# v6.net
KiCad netlist of a schematic drawn in EAGLE
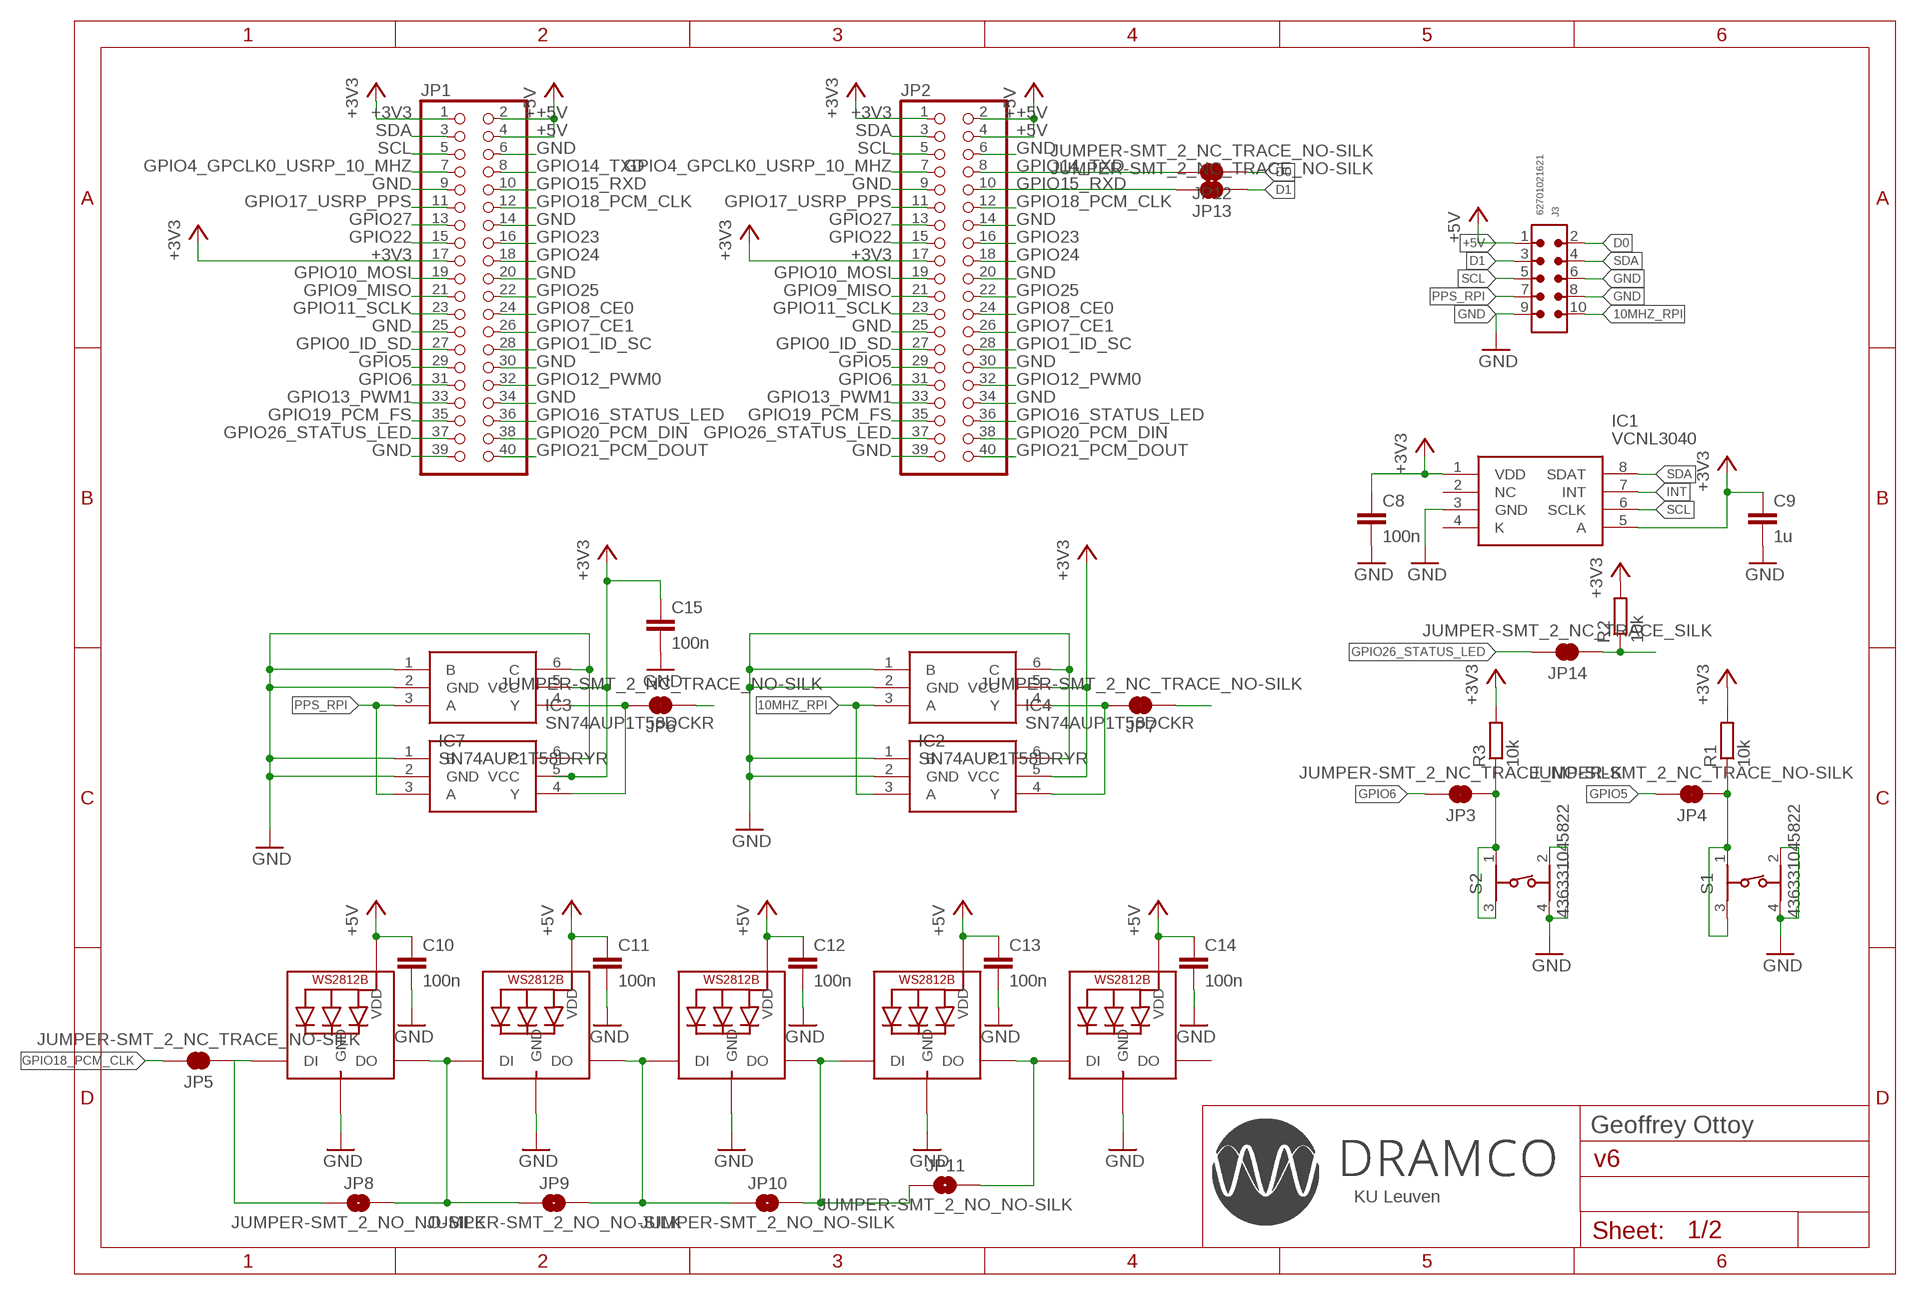
[diagram p0: schematic, sheet 1]
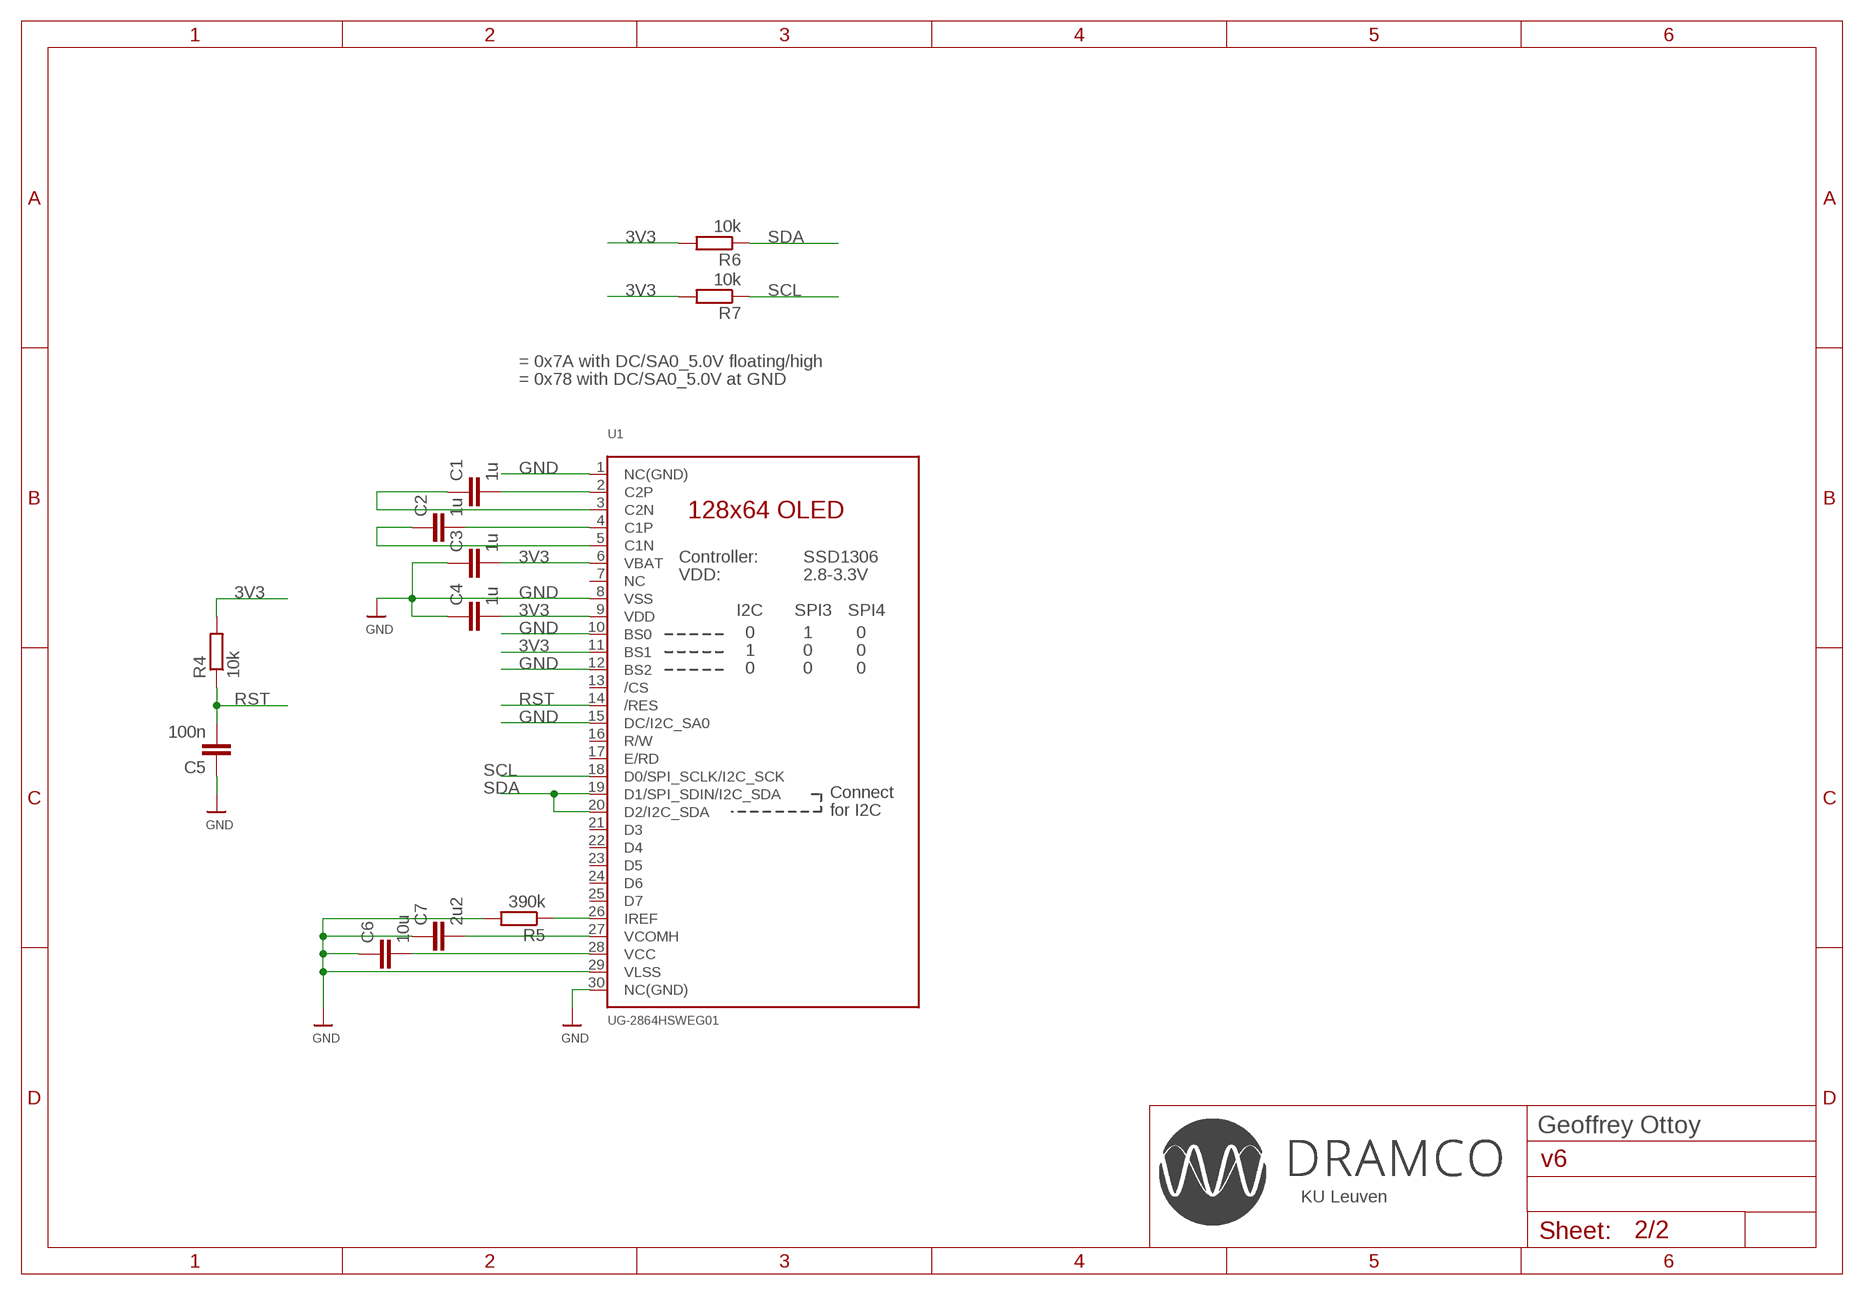
[diagram p1: schematic, sheet 2]

(export (version "E")
  (design (tool "Eeschema 10.0.6"))
  (components
    (comp (ref "C1")
      (value "1u")
      (footprint "eagle-import:C0603")
      (libsource (lib "eagle-import") (part "C-EUC0603"))
    )
    (comp (ref "C2")
      (value "1u")
      (footprint "eagle-import:C0603")
      (libsource (lib "eagle-import") (part "C-EUC0603"))
    )
    (comp (ref "C3")
      (value "1u")
      (footprint "eagle-import:C0603")
      (libsource (lib "eagle-import") (part "C-EUC0603"))
    )
    (comp (ref "C4")
      (value "1u")
      (footprint "eagle-import:C0603")
      (libsource (lib "eagle-import") (part "C-EUC0603"))
    )
    (comp (ref "C5")
      (value "100n")
      (footprint "eagle-import:C0603")
      (libsource (lib "eagle-import") (part "C-EUC0603"))
    )
    (comp (ref "C6")
      (value "10u")
      (footprint "eagle-import:C0603")
      (libsource (lib "eagle-import") (part "C-EUC0603"))
    )
    (comp (ref "C7")
      (value "2u2")
      (footprint "eagle-import:C0603")
      (libsource (lib "eagle-import") (part "C-EUC0603"))
    )
    (comp (ref "R4")
      (value "10k")
      (footprint "eagle-import:R0603")
      (libsource (lib "eagle-import") (part "R-EU_R0603"))
    )
    (comp (ref "R5")
      (value "390k")
      (footprint "eagle-import:R0603")
      (libsource (lib "eagle-import") (part "R-EU_R0603"))
    )
    (comp (ref "R6")
      (value "10k")
      (footprint "eagle-import:R0603")
      (libsource (lib "eagle-import") (part "R-EU_R0603"))
    )
    (comp (ref "R7")
      (value "10k")
      (footprint "eagle-import:R0603")
      (libsource (lib "eagle-import") (part "R-EU_R0603"))
    )
    (comp (ref "U1")
      (value "UG-2864HSWEG01")
      (footprint "eagle-import:UG-2864HSWEG01_0.96IN_WRAPAROUND")
      (libsource (lib "eagle-import") (part "DISP_OLED_UG-2864HSWEG010.96{dblquote}"))
    )
    (comp (ref "C8")
      (value "100n")
      (footprint "eagle-import:C0603")
      (libsource (lib "eagle-import") (part "C-EUC0603"))
    )
    (comp (ref "C9")
      (value "1u")
      (footprint "eagle-import:C0603")
      (libsource (lib "eagle-import") (part "C-EUC0603"))
    )
    (comp (ref "C10")
      (value "100n")
      (footprint "eagle-import:C0603")
      (libsource (lib "eagle-import") (part "C-EUC0603"))
    )
    (comp (ref "C11")
      (value "100n")
      (footprint "eagle-import:C0603")
      (libsource (lib "eagle-import") (part "C-EUC0603"))
    )
    (comp (ref "C12")
      (value "100n")
      (footprint "eagle-import:C0603")
      (libsource (lib "eagle-import") (part "C-EUC0603"))
    )
    (comp (ref "C13")
      (value "100n")
      (footprint "eagle-import:C0603")
      (libsource (lib "eagle-import") (part "C-EUC0603"))
    )
    (comp (ref "C14")
      (value "100n")
      (footprint "eagle-import:C0603")
      (libsource (lib "eagle-import") (part "C-EUC0603"))
    )
    (comp (ref "C15")
      (value "100n")
      (footprint "eagle-import:C0603")
      (libsource (lib "eagle-import") (part "C-EUC0603"))
    )
    (comp (ref "IC1")
      (value "VCNL3040")
      (footprint "eagle-import:SON108P200X400X115-8N")
      (fields (field (name "MOUSER_PART_NUMBER") "78-VCNL3040"))
      (libsource (lib "eagle-import") (part "VCNL3040"))
    )
    (comp (ref "IC2")
      (value "SN74AUP1T58DRYR")
      (footprint "eagle-import:SON50P100X145X60-6N")
      (libsource (lib "eagle-import") (part "SN74AUP1T58DRYR"))
    )
    (comp (ref "IC3")
      (value "SN74AUP1T58DCKR")
      (footprint "eagle-import:SOT65P210X110-6N")
      (libsource (lib "eagle-import") (part "SN74AUP1T58DCKR"))
    )
    (comp (ref "IC4")
      (value "SN74AUP1T58DCKR")
      (footprint "eagle-import:SOT65P210X110-6N")
      (libsource (lib "eagle-import") (part "SN74AUP1T58DCKR"))
    )
    (comp (ref "IC7")
      (value "SN74AUP1T58DRYR")
      (footprint "eagle-import:SON50P100X145X60-6N")
      (libsource (lib "eagle-import") (part "SN74AUP1T58DRYR"))
    )
    (comp (ref "J3")
      (value "62701021621")
      (footprint "eagle-import:62701021621")
      (libsource (lib "eagle-import") (part "6270XX21621_62701021621"))
    )
    (comp (ref "JP1")
      (value "PINHD-2X20")
      (footprint "eagle-import:2X20")
      (libsource (lib "eagle-import") (part "PINHD-2X20"))
    )
    (comp (ref "JP2")
      (value "PINHD-2X20/90")
      (footprint "eagle-import:2X20_90")
      (libsource (lib "eagle-import") (part "PINHD-2X20/90"))
    )
    (comp (ref "JP3")
      (value "JUMPER-SMT_2_NC_TRACE_NO-SILK")
      (footprint "eagle-import:SMT-JUMPER_2_NC_TRACE_NO-SILK")
      (libsource (lib "eagle-import") (part "JUMPER-SMT_2_NC_TRACE_NO-SILK"))
    )
    (comp (ref "JP4")
      (value "JUMPER-SMT_2_NC_TRACE_NO-SILK")
      (footprint "eagle-import:SMT-JUMPER_2_NC_TRACE_NO-SILK")
      (libsource (lib "eagle-import") (part "JUMPER-SMT_2_NC_TRACE_NO-SILK"))
    )
    (comp (ref "JP5")
      (value "JUMPER-SMT_2_NC_TRACE_NO-SILK")
      (footprint "eagle-import:SMT-JUMPER_2_NC_TRACE_NO-SILK")
      (libsource (lib "eagle-import") (part "JUMPER-SMT_2_NC_TRACE_NO-SILK"))
    )
    (comp (ref "JP6")
      (value "JUMPER-SMT_2_NC_TRACE_NO-SILK")
      (footprint "eagle-import:SMT-JUMPER_2_NC_TRACE_NO-SILK")
      (libsource (lib "eagle-import") (part "JUMPER-SMT_2_NC_TRACE_NO-SILK"))
    )
    (comp (ref "JP7")
      (value "JUMPER-SMT_2_NC_TRACE_NO-SILK")
      (footprint "eagle-import:SMT-JUMPER_2_NC_TRACE_NO-SILK")
      (libsource (lib "eagle-import") (part "JUMPER-SMT_2_NC_TRACE_NO-SILK"))
    )
    (comp (ref "JP8")
      (value "JUMPER-SMT_2_NO_NO-SILK")
      (footprint "eagle-import:SMT-JUMPER_2_NO_NO-SILK")
      (libsource (lib "eagle-import") (part "JUMPER-SMT_2_NO_NO-SILK"))
    )
    (comp (ref "JP9")
      (value "JUMPER-SMT_2_NO_NO-SILK")
      (footprint "eagle-import:SMT-JUMPER_2_NO_NO-SILK")
      (libsource (lib "eagle-import") (part "JUMPER-SMT_2_NO_NO-SILK"))
    )
    (comp (ref "JP10")
      (value "JUMPER-SMT_2_NO_NO-SILK")
      (footprint "eagle-import:SMT-JUMPER_2_NO_NO-SILK")
      (libsource (lib "eagle-import") (part "JUMPER-SMT_2_NO_NO-SILK"))
    )
    (comp (ref "JP11")
      (value "JUMPER-SMT_2_NO_NO-SILK")
      (footprint "eagle-import:SMT-JUMPER_2_NO_NO-SILK")
      (libsource (lib "eagle-import") (part "JUMPER-SMT_2_NO_NO-SILK"))
    )
    (comp (ref "JP12")
      (value "JUMPER-SMT_2_NC_TRACE_NO-SILK")
      (footprint "eagle-import:SMT-JUMPER_2_NC_TRACE_NO-SILK")
      (libsource (lib "eagle-import") (part "JUMPER-SMT_2_NC_TRACE_NO-SILK"))
    )
    (comp (ref "JP13")
      (value "JUMPER-SMT_2_NC_TRACE_NO-SILK")
      (footprint "eagle-import:SMT-JUMPER_2_NC_TRACE_NO-SILK")
      (libsource (lib "eagle-import") (part "JUMPER-SMT_2_NC_TRACE_NO-SILK"))
    )
    (comp (ref "JP14")
      (value "JUMPER-SMT_2_NC_TRACE_SILK")
      (footprint "eagle-import:SMT-JUMPER_2_NC_TRACE_SILK")
      (libsource (lib "eagle-import") (part "JUMPER-SMT_2_NC_TRACE_SILK"))
    )
    (comp (ref "LED1")
      (value "WS2812B5050")
      (footprint "eagle-import:WS2812B")
      (libsource (lib "eagle-import") (part "WS2812B5050"))
    )
    (comp (ref "LED2")
      (value "WS2812B5050")
      (footprint "eagle-import:WS2812B")
      (libsource (lib "eagle-import") (part "WS2812B5050"))
    )
    (comp (ref "LED3")
      (value "WS2812B5050")
      (footprint "eagle-import:WS2812B")
      (libsource (lib "eagle-import") (part "WS2812B5050"))
    )
    (comp (ref "LED4")
      (value "WS2812B5050")
      (footprint "eagle-import:WS2812B")
      (libsource (lib "eagle-import") (part "WS2812B5050"))
    )
    (comp (ref "LED5")
      (value "WS2812B5050")
      (footprint "eagle-import:WS2812B")
      (libsource (lib "eagle-import") (part "WS2812B5050"))
    )
    (comp (ref "R1")
      (value "10k")
      (footprint "eagle-import:R0603")
      (libsource (lib "eagle-import") (part "R-EU_R0603"))
    )
    (comp (ref "R2")
      (value "10k")
      (footprint "eagle-import:R0603")
      (libsource (lib "eagle-import") (part "R-EU_R0603"))
    )
    (comp (ref "R3")
      (value "10k")
      (footprint "eagle-import:R0603")
      (libsource (lib "eagle-import") (part "R-EU_R0603"))
    )
    (comp (ref "S1")
      (value "436331045822")
      (footprint "eagle-import:4363X10458XX")
      (libsource (lib "eagle-import") (part "436331045822"))
    )
    (comp (ref "S2")
      (value "436331045822")
      (footprint "eagle-import:4363X10458XX")
      (libsource (lib "eagle-import") (part "436331045822"))
    )
  )
  (nets
    (net (code "1") (name "+3V3") (class "Default")
      (node (ref "C15") (pin "1") (pinfunction "1_1") (pintype "passive"))
      (node (ref "C8") (pin "1") (pinfunction "1_1") (pintype "passive"))
      (node (ref "C9") (pin "1") (pinfunction "1_1") (pintype "passive"))
      (node (ref "IC1") (pin "1") (pinfunction "VDD_1") (pintype "bidirectional"))
      (node (ref "IC1") (pin "5") (pinfunction "A_5") (pintype "bidirectional"))
      (node (ref "IC2") (pin "5") (pinfunction "VCC_5") (pintype "bidirectional"))
      (node (ref "IC3") (pin "5") (pinfunction "VCC_5") (pintype "bidirectional"))
      (node (ref "IC4") (pin "5") (pinfunction "VCC_5") (pintype "bidirectional"))
      (node (ref "IC7") (pin "5") (pinfunction "VCC_5") (pintype "bidirectional"))
      (node (ref "JP1") (pin "1") (pinfunction "1_1") (pintype "passive"))
      (node (ref "JP1") (pin "17") (pinfunction "17_17") (pintype "passive"))
      (node (ref "JP2") (pin "1") (pinfunction "1_1") (pintype "passive"))
      (node (ref "JP2") (pin "17") (pinfunction "17_17") (pintype "passive"))
      (node (ref "R1") (pin "2") (pinfunction "2_2") (pintype "passive"))
      (node (ref "R2") (pin "2") (pinfunction "2_2") (pintype "passive"))
      (node (ref "R3") (pin "2") (pinfunction "2_2") (pintype "passive"))
    )
    (net (code "2") (name "+5V") (class "Default")
      (node (ref "C10") (pin "1") (pinfunction "1_1") (pintype "passive"))
      (node (ref "C11") (pin "1") (pinfunction "1_1") (pintype "passive"))
      (node (ref "C12") (pin "1") (pinfunction "1_1") (pintype "passive"))
      (node (ref "C13") (pin "1") (pinfunction "1_1") (pintype "passive"))
      (node (ref "C14") (pin "1") (pinfunction "1_1") (pintype "passive"))
      (node (ref "J3") (pin "1") (pinfunction "1_1") (pintype "passive"))
      (node (ref "JP1") (pin "2") (pinfunction "2_2") (pintype "passive"))
      (node (ref "JP1") (pin "4") (pinfunction "4_4") (pintype "passive"))
      (node (ref "JP2") (pin "2") (pinfunction "2_2") (pintype "passive"))
      (node (ref "JP2") (pin "4") (pinfunction "4_4") (pintype "passive"))
      (node (ref "LED1") (pin "1-VDD") (pinfunction "VDD_1-VDD") (pintype "power_in"))
      (node (ref "LED2") (pin "1-VDD") (pinfunction "VDD_1-VDD") (pintype "power_in"))
      (node (ref "LED3") (pin "1-VDD") (pinfunction "VDD_1-VDD") (pintype "power_in"))
      (node (ref "LED4") (pin "1-VDD") (pinfunction "VDD_1-VDD") (pintype "power_in"))
      (node (ref "LED5") (pin "1-VDD") (pinfunction "VDD_1-VDD") (pintype "power_in"))
    )
    (net (code "3") (name "3V3") (class "Default")
      (node (ref "C3") (pin "2") (pinfunction "2_2") (pintype "passive"))
      (node (ref "C4") (pin "2") (pinfunction "2_2") (pintype "passive"))
      (node (ref "R4") (pin "2") (pinfunction "2_2") (pintype "passive"))
      (node (ref "R6") (pin "2") (pinfunction "2_2") (pintype "passive"))
      (node (ref "R7") (pin "2") (pinfunction "2_2") (pintype "passive"))
      (node (ref "U1") (pin "11") (pinfunction "BS1_11") (pintype "input"))
      (node (ref "U1") (pin "6") (pinfunction "VBAT_6") (pintype "input"))
      (node (ref "U1") (pin "9") (pinfunction "VDD_9") (pintype "power_in"))
    )
    (net (code "4") (name "10MHZ_RPI") (class "Default")
      (node (ref "IC2") (pin "3") (pinfunction "A_3") (pintype "bidirectional"))
      (node (ref "IC4") (pin "3") (pinfunction "A_3") (pintype "bidirectional"))
      (node (ref "J3") (pin "10") (pinfunction "10_10") (pintype "passive"))
    )
    (net (code "5") (name "D0") (class "Default")
      (node (ref "J3") (pin "2") (pinfunction "2_2") (pintype "passive"))
      (node (ref "JP12") (pin "1") (pinfunction "1_1") (pintype "passive"))
    )
    (net (code "6") (name "D1") (class "Default")
      (node (ref "J3") (pin "3") (pinfunction "3_3") (pintype "passive"))
      (node (ref "JP13") (pin "1") (pinfunction "1_1") (pintype "passive"))
    )
    (net (code "7") (name "GND") (class "Default")
      (node (ref "C10") (pin "2") (pinfunction "2_2") (pintype "passive"))
      (node (ref "C11") (pin "2") (pinfunction "2_2") (pintype "passive"))
      (node (ref "C12") (pin "2") (pinfunction "2_2") (pintype "passive"))
      (node (ref "C13") (pin "2") (pinfunction "2_2") (pintype "passive"))
      (node (ref "C14") (pin "2") (pinfunction "2_2") (pintype "passive"))
      (node (ref "C15") (pin "2") (pinfunction "2_2") (pintype "passive"))
      (node (ref "C3") (pin "1") (pinfunction "1_1") (pintype "passive"))
      (node (ref "C4") (pin "1") (pinfunction "1_1") (pintype "passive"))
      (node (ref "C5") (pin "1") (pinfunction "1_1") (pintype "passive"))
      (node (ref "C6") (pin "1") (pinfunction "1_1") (pintype "passive"))
      (node (ref "C7") (pin "1") (pinfunction "1_1") (pintype "passive"))
      (node (ref "C8") (pin "2") (pinfunction "2_2") (pintype "passive"))
      (node (ref "C9") (pin "2") (pinfunction "2_2") (pintype "passive"))
      (node (ref "IC1") (pin "3") (pinfunction "GND_3") (pintype "bidirectional"))
      (node (ref "IC2") (pin "1") (pinfunction "B_1") (pintype "bidirectional"))
      (node (ref "IC2") (pin "2") (pinfunction "GND_2") (pintype "bidirectional"))
      (node (ref "IC2") (pin "6") (pinfunction "C_6") (pintype "bidirectional"))
      (node (ref "IC3") (pin "1") (pinfunction "B_1") (pintype "bidirectional"))
      (node (ref "IC3") (pin "2") (pinfunction "GND_2") (pintype "bidirectional"))
      (node (ref "IC3") (pin "6") (pinfunction "C_6") (pintype "bidirectional"))
      (node (ref "IC4") (pin "1") (pinfunction "B_1") (pintype "bidirectional"))
      (node (ref "IC4") (pin "2") (pinfunction "GND_2") (pintype "bidirectional"))
      (node (ref "IC4") (pin "6") (pinfunction "C_6") (pintype "bidirectional"))
      (node (ref "IC7") (pin "1") (pinfunction "B_1") (pintype "bidirectional"))
      (node (ref "IC7") (pin "2") (pinfunction "GND_2") (pintype "bidirectional"))
      (node (ref "IC7") (pin "6") (pinfunction "C_6") (pintype "bidirectional"))
      (node (ref "J3") (pin "6") (pinfunction "6_6") (pintype "passive"))
      (node (ref "J3") (pin "8") (pinfunction "8_8") (pintype "passive"))
      (node (ref "J3") (pin "9") (pinfunction "9_9") (pintype "passive"))
      (node (ref "JP1") (pin "14") (pinfunction "14_14") (pintype "passive"))
      (node (ref "JP1") (pin "20") (pinfunction "20_20") (pintype "passive"))
      (node (ref "JP1") (pin "25") (pinfunction "25_25") (pintype "passive"))
      (node (ref "JP1") (pin "30") (pinfunction "30_30") (pintype "passive"))
      (node (ref "JP1") (pin "34") (pinfunction "34_34") (pintype "passive"))
      (node (ref "JP1") (pin "39") (pinfunction "39_39") (pintype "passive"))
      (node (ref "JP1") (pin "6") (pinfunction "6_6") (pintype "passive"))
      (node (ref "JP1") (pin "9") (pinfunction "9_9") (pintype "passive"))
      (node (ref "JP2") (pin "14") (pinfunction "14_14") (pintype "passive"))
      (node (ref "JP2") (pin "20") (pinfunction "20_20") (pintype "passive"))
      (node (ref "JP2") (pin "25") (pinfunction "25_25") (pintype "passive"))
      (node (ref "JP2") (pin "30") (pinfunction "30_30") (pintype "passive"))
      (node (ref "JP2") (pin "34") (pinfunction "34_34") (pintype "passive"))
      (node (ref "JP2") (pin "39") (pinfunction "39_39") (pintype "passive"))
      (node (ref "JP2") (pin "6") (pinfunction "6_6") (pintype "passive"))
      (node (ref "JP2") (pin "9") (pinfunction "9_9") (pintype "passive"))
      (node (ref "LED1") (pin "3-GND") (pinfunction "GND_3-GND") (pintype "power_in"))
      (node (ref "LED2") (pin "3-GND") (pinfunction "GND_3-GND") (pintype "power_in"))
      (node (ref "LED3") (pin "3-GND") (pinfunction "GND_3-GND") (pintype "power_in"))
      (node (ref "LED4") (pin "3-GND") (pinfunction "GND_3-GND") (pintype "power_in"))
      (node (ref "LED5") (pin "3-GND") (pinfunction "GND_3-GND") (pintype "power_in"))
      (node (ref "R5") (pin "2") (pinfunction "2_2") (pintype "passive"))
      (node (ref "S1") (pin "2") (pinfunction "4_2") (pintype "passive"))
      (node (ref "S1") (pin "4") (pinfunction "2_4") (pintype "passive"))
      (node (ref "S2") (pin "2") (pinfunction "4_2") (pintype "passive"))
      (node (ref "S2") (pin "4") (pinfunction "2_4") (pintype "passive"))
      (node (ref "U1") (pin "1") (pinfunction "NC(GND)_1") (pintype "input"))
      (node (ref "U1") (pin "10") (pinfunction "BS0_10") (pintype "input"))
      (node (ref "U1") (pin "12") (pinfunction "BS2_12") (pintype "input"))
      (node (ref "U1") (pin "15") (pinfunction "DC/I2C_SA0_15") (pintype "input"))
      (node (ref "U1") (pin "29") (pinfunction "VLSS_29") (pintype "power_in"))
      (node (ref "U1") (pin "30") (pinfunction "NC(GND)_30") (pintype "input"))
      (node (ref "U1") (pin "8") (pinfunction "VSS_8") (pintype "power_in"))
    )
    (net (code "8") (name "GPIO0_ID_SD") (class "Default")
      (node (ref "JP1") (pin "27") (pinfunction "27_27") (pintype "passive"))
      (node (ref "JP2") (pin "27") (pinfunction "27_27") (pintype "passive"))
    )
    (net (code "9") (name "GPIO1_ID_SC") (class "Default")
      (node (ref "JP1") (pin "28") (pinfunction "28_28") (pintype "passive"))
      (node (ref "JP2") (pin "28") (pinfunction "28_28") (pintype "passive"))
    )
    (net (code "10") (name "GPIO4_GPCLK0_USRP_10_MHZ") (class "Default")
      (node (ref "JP1") (pin "7") (pinfunction "7_7") (pintype "passive"))
      (node (ref "JP2") (pin "7") (pinfunction "7_7") (pintype "passive"))
      (node (ref "JP7") (pin "1") (pinfunction "1_1") (pintype "passive"))
    )
    (net (code "11") (name "GPIO5") (class "Default")
      (node (ref "JP1") (pin "29") (pinfunction "29_29") (pintype "passive"))
      (node (ref "JP2") (pin "29") (pinfunction "29_29") (pintype "passive"))
      (node (ref "JP4") (pin "2") (pinfunction "2_2") (pintype "passive"))
    )
    (net (code "12") (name "GPIO6") (class "Default")
      (node (ref "JP1") (pin "31") (pinfunction "31_31") (pintype "passive"))
      (node (ref "JP2") (pin "31") (pinfunction "31_31") (pintype "passive"))
      (node (ref "JP3") (pin "2") (pinfunction "2_2") (pintype "passive"))
    )
    (net (code "13") (name "GPIO7_CE1") (class "Default")
      (node (ref "JP1") (pin "26") (pinfunction "26_26") (pintype "passive"))
      (node (ref "JP2") (pin "26") (pinfunction "26_26") (pintype "passive"))
    )
    (net (code "14") (name "GPIO8_CE0") (class "Default")
      (node (ref "JP1") (pin "24") (pinfunction "24_24") (pintype "passive"))
      (node (ref "JP2") (pin "24") (pinfunction "24_24") (pintype "passive"))
    )
    (net (code "15") (name "GPIO9_MISO") (class "Default")
      (node (ref "JP1") (pin "21") (pinfunction "21_21") (pintype "passive"))
      (node (ref "JP2") (pin "21") (pinfunction "21_21") (pintype "passive"))
    )
    (net (code "16") (name "GPIO10_MOSI") (class "Default")
      (node (ref "JP1") (pin "19") (pinfunction "19_19") (pintype "passive"))
      (node (ref "JP2") (pin "19") (pinfunction "19_19") (pintype "passive"))
    )
    (net (code "17") (name "GPIO11_SCLK") (class "Default")
      (node (ref "JP1") (pin "23") (pinfunction "23_23") (pintype "passive"))
      (node (ref "JP2") (pin "23") (pinfunction "23_23") (pintype "passive"))
    )
    (net (code "18") (name "GPIO12_PWM0") (class "Default")
      (node (ref "JP1") (pin "32") (pinfunction "32_32") (pintype "passive"))
      (node (ref "JP2") (pin "32") (pinfunction "32_32") (pintype "passive"))
    )
    (net (code "19") (name "GPIO13_PWM1") (class "Default")
      (node (ref "JP1") (pin "33") (pinfunction "33_33") (pintype "passive"))
      (node (ref "JP2") (pin "33") (pinfunction "33_33") (pintype "passive"))
    )
    (net (code "20") (name "GPIO14_TXD") (class "Default")
      (node (ref "JP1") (pin "8") (pinfunction "8_8") (pintype "passive"))
      (node (ref "JP12") (pin "2") (pinfunction "2_2") (pintype "passive"))
      (node (ref "JP2") (pin "8") (pinfunction "8_8") (pintype "passive"))
    )
    (net (code "21") (name "GPIO15_RXD") (class "Default")
      (node (ref "JP1") (pin "10") (pinfunction "10_10") (pintype "passive"))
      (node (ref "JP13") (pin "2") (pinfunction "2_2") (pintype "passive"))
      (node (ref "JP2") (pin "10") (pinfunction "10_10") (pintype "passive"))
    )
    (net (code "22") (name "GPIO16_STATUS_LED") (class "Default")
      (node (ref "JP1") (pin "36") (pinfunction "36_36") (pintype "passive"))
      (node (ref "JP2") (pin "36") (pinfunction "36_36") (pintype "passive"))
    )
    (net (code "23") (name "GPIO17_USRP_PPS") (class "Default")
      (node (ref "JP1") (pin "11") (pinfunction "11_11") (pintype "passive"))
      (node (ref "JP2") (pin "11") (pinfunction "11_11") (pintype "passive"))
      (node (ref "JP6") (pin "1") (pinfunction "1_1") (pintype "passive"))
    )
    (net (code "24") (name "GPIO18_PCM_CLK") (class "Default")
      (node (ref "JP1") (pin "12") (pinfunction "12_12") (pintype "passive"))
      (node (ref "JP2") (pin "12") (pinfunction "12_12") (pintype "passive"))
      (node (ref "JP5") (pin "2") (pinfunction "2_2") (pintype "passive"))
    )
    (net (code "25") (name "GPIO19_PCM_FS") (class "Default")
      (node (ref "JP1") (pin "35") (pinfunction "35_35") (pintype "passive"))
      (node (ref "JP2") (pin "35") (pinfunction "35_35") (pintype "passive"))
    )
    (net (code "26") (name "GPIO20_PCM_DIN") (class "Default")
      (node (ref "JP1") (pin "38") (pinfunction "38_38") (pintype "passive"))
      (node (ref "JP2") (pin "38") (pinfunction "38_38") (pintype "passive"))
    )
    (net (code "27") (name "GPIO21_PCM_DOUT") (class "Default")
      (node (ref "JP1") (pin "40") (pinfunction "40_40") (pintype "passive"))
      (node (ref "JP2") (pin "40") (pinfunction "40_40") (pintype "passive"))
    )
    (net (code "28") (name "GPIO22") (class "Default")
      (node (ref "JP1") (pin "15") (pinfunction "15_15") (pintype "passive"))
      (node (ref "JP2") (pin "15") (pinfunction "15_15") (pintype "passive"))
    )
    (net (code "29") (name "GPIO23") (class "Default")
      (node (ref "JP1") (pin "16") (pinfunction "16_16") (pintype "passive"))
      (node (ref "JP2") (pin "16") (pinfunction "16_16") (pintype "passive"))
    )
    (net (code "30") (name "GPIO24") (class "Default")
      (node (ref "JP1") (pin "18") (pinfunction "18_18") (pintype "passive"))
      (node (ref "JP2") (pin "18") (pinfunction "18_18") (pintype "passive"))
    )
    (net (code "31") (name "GPIO25") (class "Default")
      (node (ref "JP1") (pin "22") (pinfunction "22_22") (pintype "passive"))
      (node (ref "JP2") (pin "22") (pinfunction "22_22") (pintype "passive"))
    )
    (net (code "32") (name "GPIO26_STATUS_LED") (class "Default")
      (node (ref "JP1") (pin "37") (pinfunction "37_37") (pintype "passive"))
      (node (ref "JP14") (pin "2") (pinfunction "2_2") (pintype "passive"))
      (node (ref "JP2") (pin "37") (pinfunction "37_37") (pintype "passive"))
    )
    (net (code "33") (name "GPIO27") (class "Default")
      (node (ref "JP1") (pin "13") (pinfunction "13_13") (pintype "passive"))
      (node (ref "JP2") (pin "13") (pinfunction "13_13") (pintype "passive"))
    )
    (net (code "34") (name "INT") (class "Default")
      (node (ref "IC1") (pin "7") (pinfunction "INT_7") (pintype "bidirectional"))
      (node (ref "JP14") (pin "1") (pinfunction "1_1") (pintype "passive"))
      (node (ref "R2") (pin "1") (pinfunction "1_1") (pintype "passive"))
    )
    (net (code "35") (name "Net-(IC2-Y)") (class "Default")
      (node (ref "IC2") (pin "4") (pinfunction "Y_4") (pintype "bidirectional"))
      (node (ref "IC4") (pin "4") (pinfunction "Y_4") (pintype "bidirectional"))
      (node (ref "JP7") (pin "2") (pinfunction "2_2") (pintype "passive"))
    )
    (net (code "36") (name "Net-(IC3-Y)") (class "Default")
      (node (ref "IC3") (pin "4") (pinfunction "Y_4") (pintype "bidirectional"))
      (node (ref "IC7") (pin "4") (pinfunction "Y_4") (pintype "bidirectional"))
      (node (ref "JP6") (pin "2") (pinfunction "2_2") (pintype "passive"))
    )
    (net (code "37") (name "Net-(LED1-DI)") (class "Default")
      (node (ref "JP5") (pin "1") (pinfunction "1_1") (pintype "passive"))
      (node (ref "JP8") (pin "1") (pinfunction "1_1") (pintype "passive"))
      (node (ref "LED1") (pin "4-DIN") (pinfunction "DI_4-DIN") (pintype "input"))
    )
    (net (code "38") (name "Net-(LED1-DO)") (class "Default")
      (node (ref "JP8") (pin "2") (pinfunction "2_2") (pintype "passive"))
      (node (ref "JP9") (pin "1") (pinfunction "1_1") (pintype "passive"))
      (node (ref "LED1") (pin "2-DOUT") (pinfunction "DO_2-DOUT") (pintype "output"))
      (node (ref "LED2") (pin "4-DIN") (pinfunction "DI_4-DIN") (pintype "input"))
    )
    (net (code "39") (name "Net-(LED2-DO)") (class "Default")
      (node (ref "JP10") (pin "1") (pinfunction "1_1") (pintype "passive"))
      (node (ref "JP9") (pin "2") (pinfunction "2_2") (pintype "passive"))
      (node (ref "LED2") (pin "2-DOUT") (pinfunction "DO_2-DOUT") (pintype "output"))
      (node (ref "LED3") (pin "4-DIN") (pinfunction "DI_4-DIN") (pintype "input"))
    )
    (net (code "40") (name "Net-(LED3-DO)") (class "Default")
      (node (ref "JP10") (pin "2") (pinfunction "2_2") (pintype "passive"))
      (node (ref "JP11") (pin "1") (pinfunction "1_1") (pintype "passive"))
      (node (ref "LED3") (pin "2-DOUT") (pinfunction "DO_2-DOUT") (pintype "output"))
      (node (ref "LED4") (pin "4-DIN") (pinfunction "DI_4-DIN") (pintype "input"))
    )
    (net (code "41") (name "Net-(LED4-DO)") (class "Default")
      (node (ref "JP11") (pin "2") (pinfunction "2_2") (pintype "passive"))
      (node (ref "LED4") (pin "2-DOUT") (pinfunction "DO_2-DOUT") (pintype "output"))
      (node (ref "LED5") (pin "4-DIN") (pinfunction "DI_4-DIN") (pintype "input"))
    )
    (net (code "42") (name "Net-(S1-1)") (class "Default")
      (node (ref "JP4") (pin "1") (pinfunction "1_1") (pintype "passive"))
      (node (ref "R1") (pin "1") (pinfunction "1_1") (pintype "passive"))
      (node (ref "S1") (pin "1") (pinfunction "3_1") (pintype "passive"))
      (node (ref "S1") (pin "3") (pinfunction "1_3") (pintype "passive"))
    )
    (net (code "43") (name "Net-(S2-1)") (class "Default")
      (node (ref "JP3") (pin "1") (pinfunction "1_1") (pintype "passive"))
      (node (ref "R3") (pin "1") (pinfunction "1_1") (pintype "passive"))
      (node (ref "S2") (pin "1") (pinfunction "3_1") (pintype "passive"))
      (node (ref "S2") (pin "3") (pinfunction "1_3") (pintype "passive"))
    )
    (net (code "44") (name "Net-(U1-C1N)") (class "Default")
      (node (ref "C2") (pin "1") (pinfunction "1_1") (pintype "passive"))
      (node (ref "U1") (pin "5") (pinfunction "C1N_5") (pintype "input"))
    )
    (net (code "45") (name "Net-(U1-C1P)") (class "Default")
      (node (ref "C2") (pin "2") (pinfunction "2_2") (pintype "passive"))
      (node (ref "U1") (pin "4") (pinfunction "C1P_4") (pintype "input"))
    )
    (net (code "46") (name "Net-(U1-C2N)") (class "Default")
      (node (ref "C1") (pin "1") (pinfunction "1_1") (pintype "passive"))
      (node (ref "U1") (pin "3") (pinfunction "C2N_3") (pintype "input"))
    )
    (net (code "47") (name "Net-(U1-C2P)") (class "Default")
      (node (ref "C1") (pin "2") (pinfunction "2_2") (pintype "passive"))
      (node (ref "U1") (pin "2") (pinfunction "C2P_2") (pintype "input"))
    )
    (net (code "48") (name "Net-(U1-IREF)") (class "Default")
      (node (ref "R5") (pin "1") (pinfunction "1_1") (pintype "passive"))
      (node (ref "U1") (pin "26") (pinfunction "IREF_26") (pintype "input"))
    )
    (net (code "49") (name "Net-(U1-VCC)") (class "Default")
      (node (ref "C6") (pin "2") (pinfunction "2_2") (pintype "passive"))
      (node (ref "U1") (pin "28") (pinfunction "VCC_28") (pintype "power_in"))
    )
    (net (code "50") (name "Net-(U1-VCOMH)") (class "Default")
      (node (ref "C7") (pin "2") (pinfunction "2_2") (pintype "passive"))
      (node (ref "U1") (pin "27") (pinfunction "VCOMH_27") (pintype "output"))
    )
    (net (code "51") (name "PPS_RPI") (class "Default")
      (node (ref "IC3") (pin "3") (pinfunction "A_3") (pintype "bidirectional"))
      (node (ref "IC7") (pin "3") (pinfunction "A_3") (pintype "bidirectional"))
      (node (ref "J3") (pin "7") (pinfunction "7_7") (pintype "passive"))
    )
    (net (code "52") (name "RST") (class "Default")
      (node (ref "C5") (pin "2") (pinfunction "2_2") (pintype "passive"))
      (node (ref "R4") (pin "1") (pinfunction "1_1") (pintype "passive"))
      (node (ref "U1") (pin "14") (pinfunction "/RES_14") (pintype "input"))
    )
    (net (code "53") (name "SCL") (class "Default")
      (node (ref "IC1") (pin "6") (pinfunction "SCLK_6") (pintype "bidirectional"))
      (node (ref "J3") (pin "5") (pinfunction "5_5") (pintype "passive"))
      (node (ref "JP1") (pin "5") (pinfunction "5_5") (pintype "passive"))
      (node (ref "JP2") (pin "5") (pinfunction "5_5") (pintype "passive"))
      (node (ref "R7") (pin "1") (pinfunction "1_1") (pintype "passive"))
      (node (ref "U1") (pin "18") (pinfunction "D0/SPI_SCLK/I2C_SCK_18") (pintype "bidirectional"))
    )
    (net (code "54") (name "SDA") (class "Default")
      (node (ref "IC1") (pin "8") (pinfunction "SDAT_8") (pintype "bidirectional"))
      (node (ref "J3") (pin "4") (pinfunction "4_4") (pintype "passive"))
      (node (ref "JP1") (pin "3") (pinfunction "3_3") (pintype "passive"))
      (node (ref "JP2") (pin "3") (pinfunction "3_3") (pintype "passive"))
      (node (ref "R6") (pin "1") (pinfunction "1_1") (pintype "passive"))
      (node (ref "U1") (pin "19") (pinfunction "D1/SPI_SDIN/I2C_SDA_19") (pintype "bidirectional"))
      (node (ref "U1") (pin "20") (pinfunction "D2/I2C_SDA_20") (pintype "bidirectional"))
    )
    (net (code "55") (name "unconnected-(IC1-K-Pad4)") (class "Default")
      (node (ref "IC1") (pin "4") (pinfunction "K_4") (pintype "bidirectional"))
    )
    (net (code "56") (name "unconnected-(IC1-NC-Pad2)") (class "Default")
      (node (ref "IC1") (pin "2") (pinfunction "NC_2") (pintype "no_connect"))
    )
    (net (code "57") (name "unconnected-(LED5-DO-Pad2-DOUT)") (class "Default")
      (node (ref "LED5") (pin "2-DOUT") (pinfunction "DO_2-DOUT") (pintype "output"))
    )
    (net (code "58") (name "unconnected-(U1-D3-Pad21)") (class "Default")
      (node (ref "U1") (pin "21") (pinfunction "D3_21") (pintype "bidirectional"))
    )
    (net (code "59") (name "unconnected-(U1-D4-Pad22)") (class "Default")
      (node (ref "U1") (pin "22") (pinfunction "D4_22") (pintype "bidirectional"))
    )
    (net (code "60") (name "unconnected-(U1-D5-Pad23)") (class "Default")
      (node (ref "U1") (pin "23") (pinfunction "D5_23") (pintype "bidirectional"))
    )
    (net (code "61") (name "unconnected-(U1-D6-Pad24)") (class "Default")
      (node (ref "U1") (pin "24") (pinfunction "D6_24") (pintype "bidirectional"))
    )
    (net (code "62") (name "unconnected-(U1-D7-Pad25)") (class "Default")
      (node (ref "U1") (pin "25") (pinfunction "D7_25") (pintype "bidirectional"))
    )
    (net (code "63") (name "unconnected-(U1-E{slash}RD-Pad17)") (class "Default")
      (node (ref "U1") (pin "17") (pinfunction "E/RD_17") (pintype "input"))
    )
    (net (code "64") (name "unconnected-(U1-NC-Pad7)") (class "Default")
      (node (ref "U1") (pin "7") (pinfunction "NC_7") (pintype "no_connect"))
    )
    (net (code "65") (name "unconnected-(U1-R{slash}W-Pad16)") (class "Default")
      (node (ref "U1") (pin "16") (pinfunction "R/W_16") (pintype "input"))
    )
    (net (code "66") (name "unconnected-(U1-{slash}CS-Pad13)") (class "Default")
      (node (ref "U1") (pin "13") (pinfunction "/CS_13") (pintype "input"))
    )
  )
)
